# FLASH.net
KiCad netlist of a schematic drawn in Altium Designer
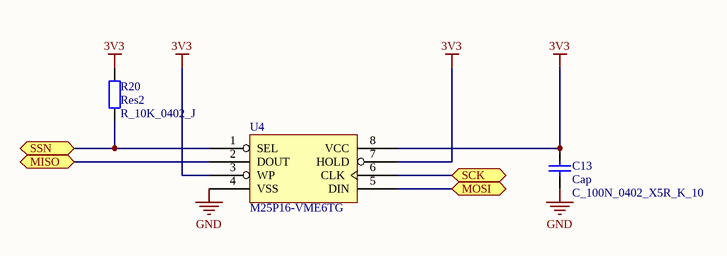
[diagram p0: FLASH.SchDoc]

(export (version "E")
  (design (tool "Eeschema 10.0.6"))
  (components
    (comp (ref "C13")
      (value "Cap")
      (footprint "C_0402")
      (description "Capacitor")
      (fields
        (field (name "ALTIUM_VALUE") "C_100N_0402_X5R_K_10")
        (field (name "PUBLISHER") "Altium Limited")
      )
      (libsource (lib "Miscellaneous Devices") (part "Cap"))
    )
    (comp (ref "R20")
      (value "Res2")
      (footprint "R_0402")
      (description "Resistor")
      (fields (field (name "ALTIUM_VALUE") "R_10K_0402_J") (field (name "PUBLISHER") "Altium Limited"))
      (libsource (lib "Miscellaneous Devices") (part "Res2"))
    )
    (comp (ref "U4")
      (value "M25P16-VME6TG")
      (footprint "VQFNPN8")
      (description "IC FLASH 16MBIT 75MHZ 8VDFPN")
      (fields (field (name "MANUFACTURER") "Micron Technology Inc"))
      (libsource (lib "BrewBit") (part "M25P16-VME6TG"))
    )
  )
  (nets
    (net (code "1") (name "/MISO") (class "Default")
      (node (ref "U4") (pin "2") (pinfunction "DOUT_2") (pintype "passive"))
    )
    (net (code "2") (name "/MOSI") (class "Default")
      (node (ref "U4") (pin "5") (pinfunction "DIN_5") (pintype "passive"))
    )
    (net (code "3") (name "/SCK") (class "Default")
      (node (ref "U4") (pin "6") (pinfunction "CLK_6") (pintype "passive"))
    )
    (net (code "4") (name "/SSN") (class "Default")
      (node (ref "R20") (pin "1") (pinfunction "1_1") (pintype "passive"))
      (node (ref "U4") (pin "1") (pinfunction "SEL_1") (pintype "passive"))
    )
    (net (code "5") (name "3V3") (class "Default")
      (node (ref "C13") (pin "2") (pinfunction "2_2") (pintype "passive"))
      (node (ref "R20") (pin "2") (pinfunction "2_2") (pintype "passive"))
      (node (ref "U4") (pin "3") (pinfunction "WP_3") (pintype "passive"))
      (node (ref "U4") (pin "7") (pinfunction "HOLD_7") (pintype "passive"))
      (node (ref "U4") (pin "8") (pinfunction "VCC_8") (pintype "passive"))
    )
    (net (code "6") (name "GND") (class "Default")
      (node (ref "C13") (pin "1") (pinfunction "1_1") (pintype "passive"))
      (node (ref "U4") (pin "4") (pinfunction "VSS_4") (pintype "passive"))
    )
  )
)
